# Mounting_PCB_LED.net
KiCad netlist of a schematic drawn in Altium Designer
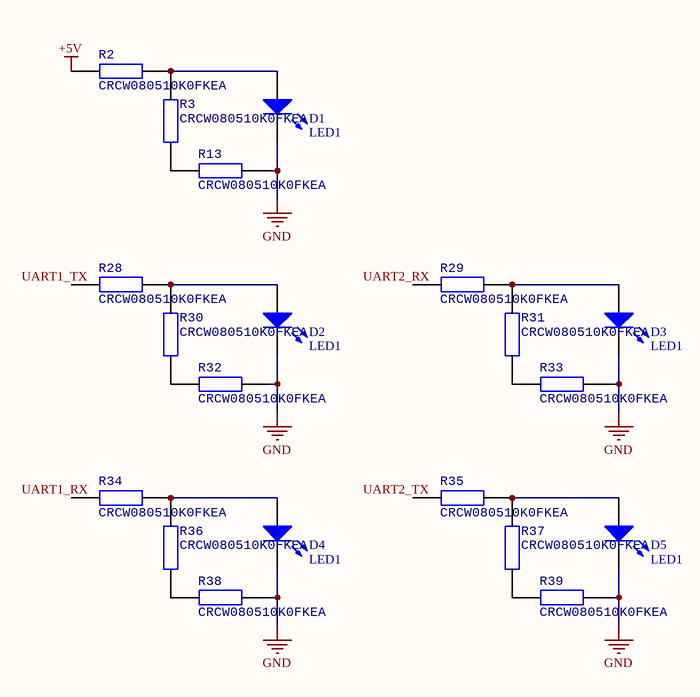
[diagram p0: Mounting_PCB_LED.SchDoc]

(export (version "E")
  (design (tool "Eeschema 10.0.6"))
  (components
    (comp (ref "D1")
      (value "LED1")
      (footprint "L0603")
      (description "Typical RED GaAs LED")
      (fields (field (name "PUBLISHER") "Altium Limited"))
      (libsource (lib "Miscellaneous Devices") (part "LED1"))
    )
    (comp (ref "D2")
      (value "LED1")
      (footprint "L0603")
      (description "Typical RED GaAs LED")
      (fields (field (name "PUBLISHER") "Altium Limited"))
      (libsource (lib "Miscellaneous Devices") (part "LED1"))
    )
    (comp (ref "D3")
      (value "LED1")
      (footprint "L0603")
      (description "Typical RED GaAs LED")
      (fields (field (name "PUBLISHER") "Altium Limited"))
      (libsource (lib "Miscellaneous Devices") (part "LED1"))
    )
    (comp (ref "D4")
      (value "LED1")
      (footprint "L0603")
      (description "Typical RED GaAs LED")
      (fields (field (name "PUBLISHER") "Altium Limited"))
      (libsource (lib "Miscellaneous Devices") (part "LED1"))
    )
    (comp (ref "D5")
      (value "LED1")
      (footprint "L0603")
      (description "Typical RED GaAs LED")
      (fields (field (name "PUBLISHER") "Altium Limited"))
      (libsource (lib "Miscellaneous Devices") (part "LED1"))
    )
    (comp (ref "R2")
      (value "CRCW080510K0FKEA")
      (footprint "RESC2012X50N")
      (fields (field (name "RS PART NUMBER") "1694499"))
      (libsource (lib "CRCW080510K0FKEA") (part "CRCW080510K0FKEA"))
    )
    (comp (ref "R3")
      (value "CRCW080510K0FKEA")
      (footprint "RESC2012X50N")
      (fields (field (name "RS PART NUMBER") "1694499"))
      (libsource (lib "CRCW080510K0FKEA") (part "CRCW080510K0FKEA"))
    )
    (comp (ref "R13")
      (value "CRCW080510K0FKEA")
      (footprint "RESC2012X50N")
      (fields (field (name "RS PART NUMBER") "1694499"))
      (libsource (lib "CRCW080510K0FKEA") (part "CRCW080510K0FKEA"))
    )
    (comp (ref "R28")
      (value "CRCW080510K0FKEA")
      (footprint "RESC2012X50N")
      (fields (field (name "RS PART NUMBER") "1694499"))
      (libsource (lib "CRCW080510K0FKEA") (part "CRCW080510K0FKEA"))
    )
    (comp (ref "R29")
      (value "CRCW080510K0FKEA")
      (footprint "RESC2012X50N")
      (fields (field (name "RS PART NUMBER") "1694499"))
      (libsource (lib "CRCW080510K0FKEA") (part "CRCW080510K0FKEA"))
    )
    (comp (ref "R30")
      (value "CRCW080510K0FKEA")
      (footprint "RESC2012X50N")
      (fields (field (name "RS PART NUMBER") "1694499"))
      (libsource (lib "CRCW080510K0FKEA") (part "CRCW080510K0FKEA"))
    )
    (comp (ref "R31")
      (value "CRCW080510K0FKEA")
      (footprint "RESC2012X50N")
      (fields (field (name "RS PART NUMBER") "1694499"))
      (libsource (lib "CRCW080510K0FKEA") (part "CRCW080510K0FKEA"))
    )
    (comp (ref "R32")
      (value "CRCW080510K0FKEA")
      (footprint "RESC2012X50N")
      (fields (field (name "RS PART NUMBER") "1694499"))
      (libsource (lib "CRCW080510K0FKEA") (part "CRCW080510K0FKEA"))
    )
    (comp (ref "R33")
      (value "CRCW080510K0FKEA")
      (footprint "RESC2012X50N")
      (fields (field (name "RS PART NUMBER") "1694499"))
      (libsource (lib "CRCW080510K0FKEA") (part "CRCW080510K0FKEA"))
    )
    (comp (ref "R34")
      (value "CRCW080510K0FKEA")
      (footprint "RESC2012X50N")
      (fields (field (name "RS PART NUMBER") "1694499"))
      (libsource (lib "CRCW080510K0FKEA") (part "CRCW080510K0FKEA"))
    )
    (comp (ref "R35")
      (value "CRCW080510K0FKEA")
      (footprint "RESC2012X50N")
      (fields (field (name "RS PART NUMBER") "1694499"))
      (libsource (lib "CRCW080510K0FKEA") (part "CRCW080510K0FKEA"))
    )
    (comp (ref "R36")
      (value "CRCW080510K0FKEA")
      (footprint "RESC2012X50N")
      (fields (field (name "RS PART NUMBER") "1694499"))
      (libsource (lib "CRCW080510K0FKEA") (part "CRCW080510K0FKEA"))
    )
    (comp (ref "R37")
      (value "CRCW080510K0FKEA")
      (footprint "RESC2012X50N")
      (fields (field (name "RS PART NUMBER") "1694499"))
      (libsource (lib "CRCW080510K0FKEA") (part "CRCW080510K0FKEA"))
    )
    (comp (ref "R38")
      (value "CRCW080510K0FKEA")
      (footprint "RESC2012X50N")
      (fields (field (name "RS PART NUMBER") "1694499"))
      (libsource (lib "CRCW080510K0FKEA") (part "CRCW080510K0FKEA"))
    )
    (comp (ref "R39")
      (value "CRCW080510K0FKEA")
      (footprint "RESC2012X50N")
      (fields (field (name "RS PART NUMBER") "1694499"))
      (libsource (lib "CRCW080510K0FKEA") (part "CRCW080510K0FKEA"))
    )
  )
  (nets
    (net (code "1") (name "+5V") (class "Default")
      (node (ref "R2") (pin "1") (pinfunction "1_1") (pintype "passive"))
    )
    (net (code "6") (name "GND") (class "Default")
      (node (ref "D1") (pin "2") (pinfunction "K_2") (pintype "passive"))
      (node (ref "D2") (pin "2") (pinfunction "K_2") (pintype "passive"))
      (node (ref "D3") (pin "2") (pinfunction "K_2") (pintype "passive"))
      (node (ref "D4") (pin "2") (pinfunction "K_2") (pintype "passive"))
      (node (ref "D5") (pin "2") (pinfunction "K_2") (pintype "passive"))
      (node (ref "R13") (pin "1") (pinfunction "1_1") (pintype "passive"))
      (node (ref "R32") (pin "1") (pinfunction "1_1") (pintype "passive"))
      (node (ref "R33") (pin "1") (pinfunction "1_1") (pintype "passive"))
      (node (ref "R38") (pin "1") (pinfunction "1_1") (pintype "passive"))
      (node (ref "R39") (pin "1") (pinfunction "1_1") (pintype "passive"))
    )
    (net (code "7") (name "Net-(D1-A)") (class "Default")
      (node (ref "D1") (pin "1") (pinfunction "A_1") (pintype "passive"))
      (node (ref "R2") (pin "2") (pinfunction "2_2") (pintype "passive"))
      (node (ref "R3") (pin "2") (pinfunction "2_2") (pintype "passive"))
    )
    (net (code "8") (name "Net-(D2-A)") (class "Default")
      (node (ref "D2") (pin "1") (pinfunction "A_1") (pintype "passive"))
      (node (ref "R28") (pin "2") (pinfunction "2_2") (pintype "passive"))
      (node (ref "R30") (pin "2") (pinfunction "2_2") (pintype "passive"))
    )
    (net (code "9") (name "Net-(D3-A)") (class "Default")
      (node (ref "D3") (pin "1") (pinfunction "A_1") (pintype "passive"))
      (node (ref "R29") (pin "2") (pinfunction "2_2") (pintype "passive"))
      (node (ref "R31") (pin "2") (pinfunction "2_2") (pintype "passive"))
    )
    (net (code "10") (name "Net-(D4-A)") (class "Default")
      (node (ref "D4") (pin "1") (pinfunction "A_1") (pintype "passive"))
      (node (ref "R34") (pin "2") (pinfunction "2_2") (pintype "passive"))
      (node (ref "R36") (pin "2") (pinfunction "2_2") (pintype "passive"))
    )
    (net (code "11") (name "Net-(D5-A)") (class "Default")
      (node (ref "D5") (pin "1") (pinfunction "A_1") (pintype "passive"))
      (node (ref "R35") (pin "2") (pinfunction "2_2") (pintype "passive"))
      (node (ref "R37") (pin "2") (pinfunction "2_2") (pintype "passive"))
    )
    (net (code "12") (name "Net-(R13-Pad2)") (class "Default")
      (node (ref "R13") (pin "2") (pinfunction "2_2") (pintype "passive"))
      (node (ref "R3") (pin "1") (pinfunction "1_1") (pintype "passive"))
    )
    (net (code "13") (name "Net-(R30-Pad1)") (class "Default")
      (node (ref "R30") (pin "1") (pinfunction "1_1") (pintype "passive"))
      (node (ref "R32") (pin "2") (pinfunction "2_2") (pintype "passive"))
    )
    (net (code "14") (name "Net-(R31-Pad1)") (class "Default")
      (node (ref "R31") (pin "1") (pinfunction "1_1") (pintype "passive"))
      (node (ref "R33") (pin "2") (pinfunction "2_2") (pintype "passive"))
    )
    (net (code "15") (name "Net-(R36-Pad1)") (class "Default")
      (node (ref "R36") (pin "1") (pinfunction "1_1") (pintype "passive"))
      (node (ref "R38") (pin "2") (pinfunction "2_2") (pintype "passive"))
    )
    (net (code "16") (name "Net-(R37-Pad1)") (class "Default")
      (node (ref "R37") (pin "1") (pinfunction "1_1") (pintype "passive"))
      (node (ref "R39") (pin "2") (pinfunction "2_2") (pintype "passive"))
    )
    (net (code "17") (name "unconnected-(R28-Pad1)") (class "Default")
      (node (ref "R28") (pin "1") (pinfunction "1_1") (pintype "passive"))
    )
    (net (code "18") (name "unconnected-(R29-Pad1)") (class "Default")
      (node (ref "R29") (pin "1") (pinfunction "1_1") (pintype "passive"))
    )
    (net (code "19") (name "unconnected-(R34-Pad1)") (class "Default")
      (node (ref "R34") (pin "1") (pinfunction "1_1") (pintype "passive"))
    )
    (net (code "20") (name "unconnected-(R35-Pad1)") (class "Default")
      (node (ref "R35") (pin "1") (pinfunction "1_1") (pintype "passive"))
    )
  )
)
